# Adafruit_Feather_Zero_BLE_rev_B.net
KiCad netlist of a schematic drawn in EAGLE
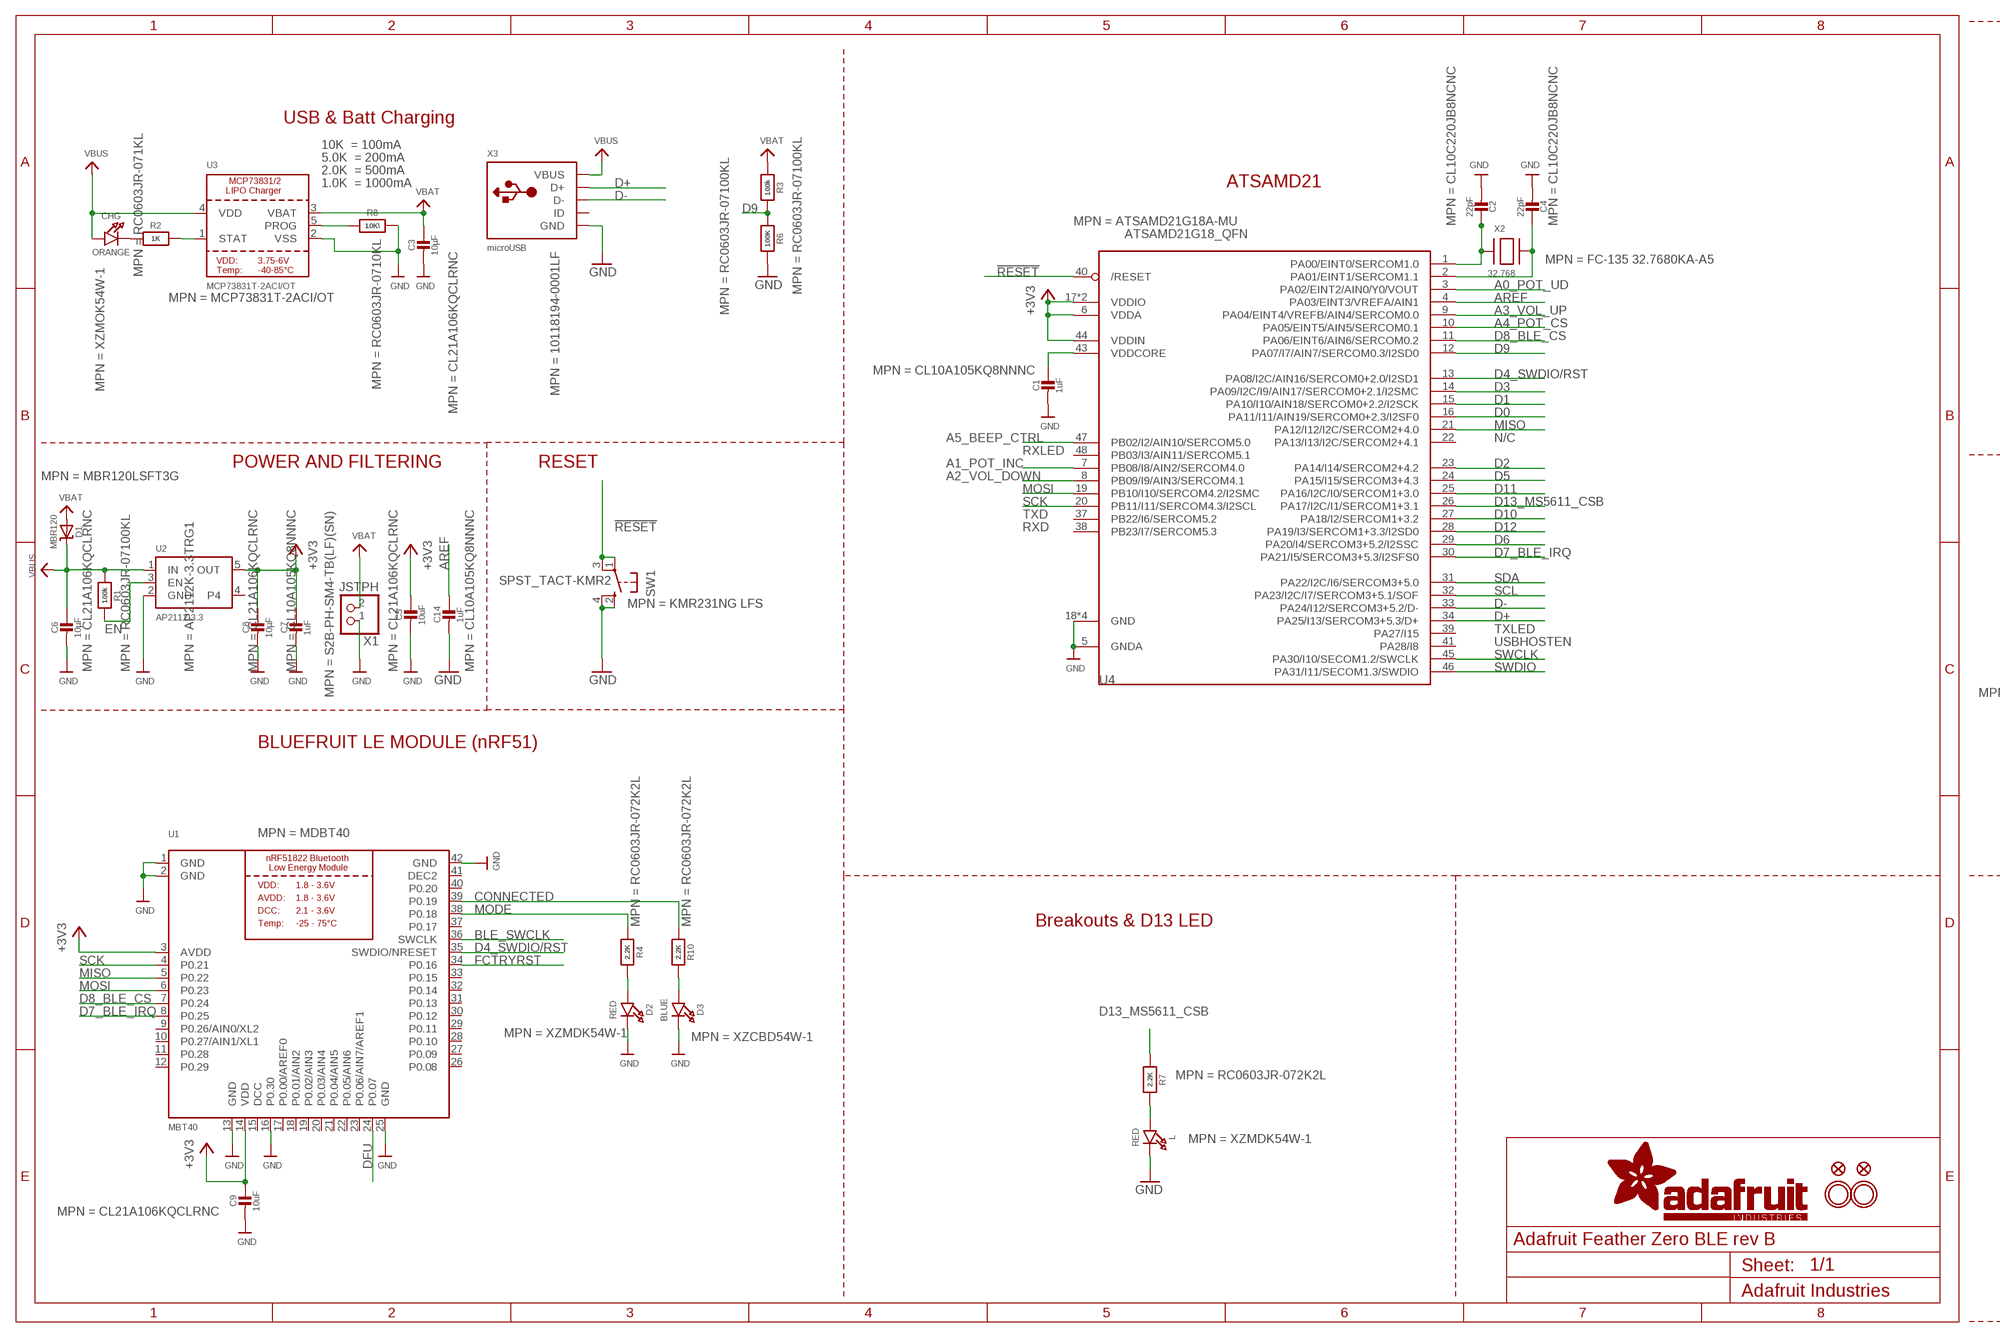
[diagram p0: schematic, sheet 1, part 1 of 2]
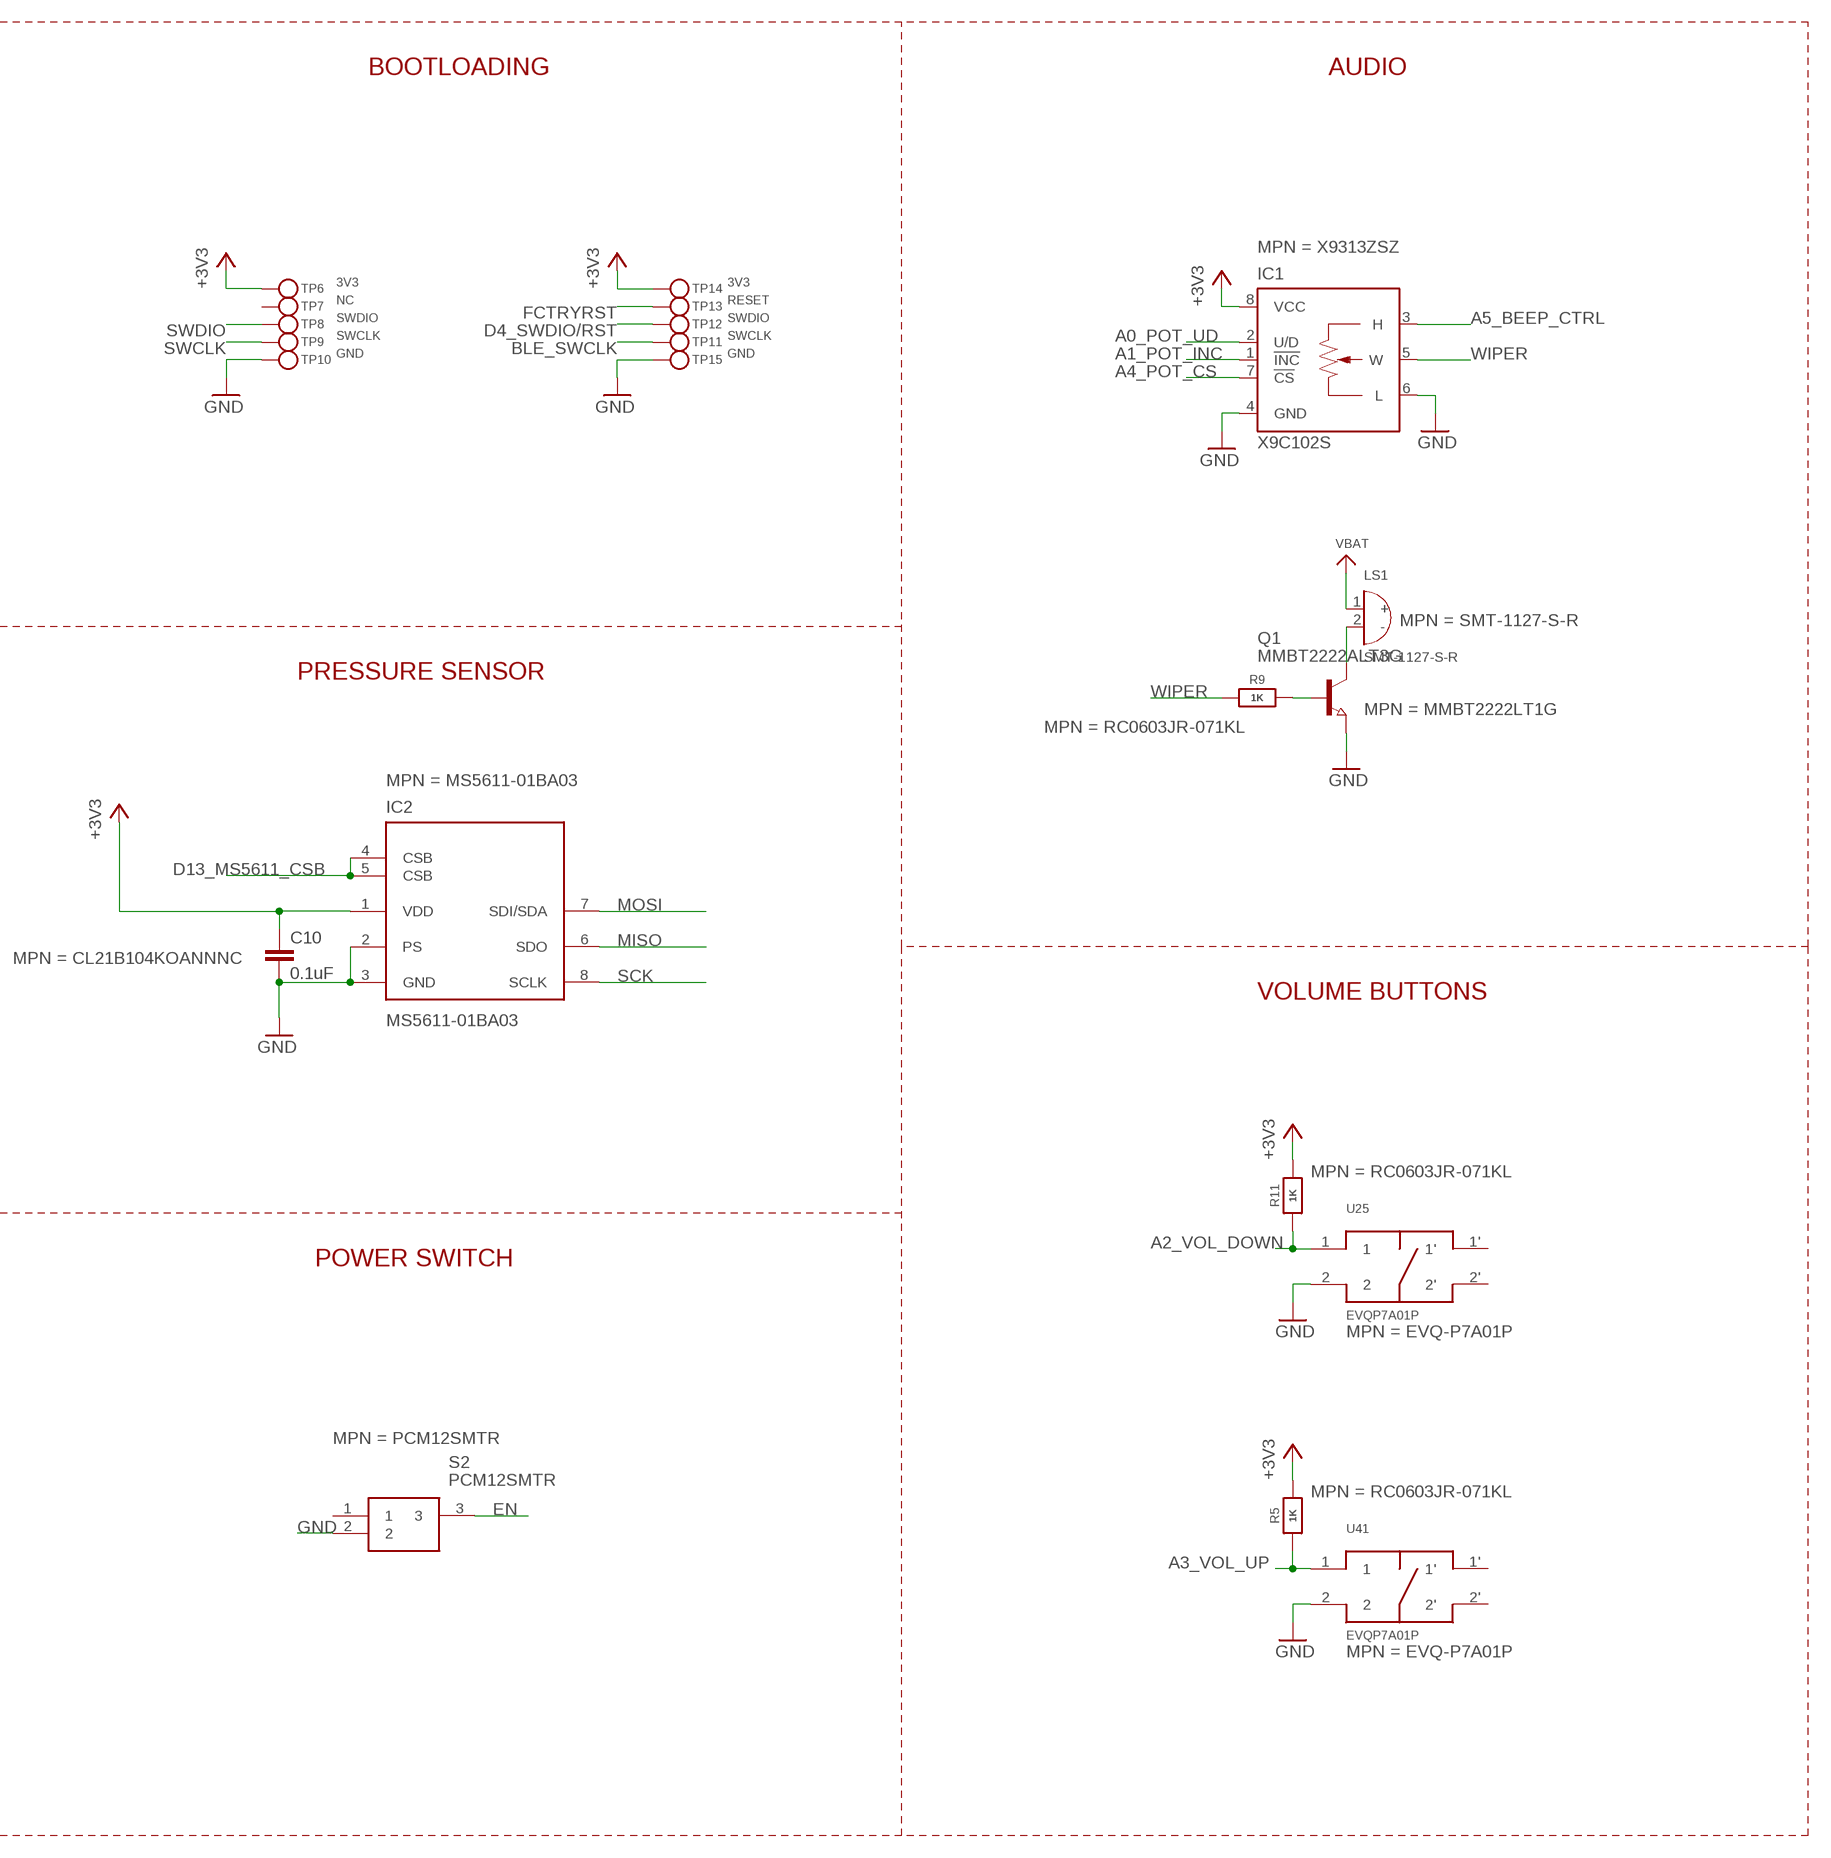
[diagram p1: schematic, sheet 1, part 2 of 2]

(export (version "E")
  (design (tool "Eeschema 10.0.6"))
  (components
    (comp (ref "C1")
      (value "1uF")
      (footprint "eagle-import:0603-NO")
      (fields (field (name "MPN") "CL10A105KQ8NNNC"))
      (libsource (lib "eagle-import") (part "CAP_CERAMIC0603_NO"))
    )
    (comp (ref "C2")
      (value "22pF")
      (footprint "eagle-import:0603-NO")
      (fields (field (name "MPN") "CL10C220JB8NCNC"))
      (libsource (lib "eagle-import") (part "CAP_CERAMIC0603_NO"))
    )
    (comp (ref "C3")
      (value "10µF")
      (footprint "eagle-import:0805-NO")
      (fields (field (name "MPN") "CL21A106KQCLRNC"))
      (libsource (lib "eagle-import") (part "CAP_CERAMIC0805-NOOUTLINE"))
    )
    (comp (ref "C4")
      (value "22pF")
      (footprint "eagle-import:0603-NO")
      (fields (field (name "MPN") "CL10C220JB8NCNC"))
      (libsource (lib "eagle-import") (part "CAP_CERAMIC0603_NO"))
    )
    (comp (ref "C5")
      (value "10uF")
      (footprint "eagle-import:0805-NO")
      (fields (field (name "MPN") "CL21A106KQCLRNC"))
      (libsource (lib "eagle-import") (part "CAP_CERAMIC0805-NOOUTLINE"))
    )
    (comp (ref "C6")
      (value "10µF")
      (footprint "eagle-import:0805-NO")
      (fields (field (name "MPN") "CL21A106KQCLRNC"))
      (libsource (lib "eagle-import") (part "CAP_CERAMIC0805-NOOUTLINE"))
    )
    (comp (ref "C7")
      (value "1uF")
      (footprint "eagle-import:0603-NO")
      (fields (field (name "MPN") "CL10A105KQ8NNNC"))
      (libsource (lib "eagle-import") (part "CAP_CERAMIC0603_NO"))
    )
    (comp (ref "C8")
      (value "10µF")
      (footprint "eagle-import:0805-NO")
      (fields (field (name "MPN") "CL21A106KQCLRNC"))
      (libsource (lib "eagle-import") (part "CAP_CERAMIC0805-NOOUTLINE"))
    )
    (comp (ref "C9")
      (value "10uF")
      (footprint "eagle-import:0805-NO")
      (fields (field (name "MPN") "CL21A106KQCLRNC"))
      (libsource (lib "eagle-import") (part "CAP_CERAMIC0805-NOOUTLINE"))
    )
    (comp (ref "C10")
      (value "0.1uF")
      (footprint "eagle-import:C0805K")
      (fields (field (name "MPN") "CL21B104KOANNNC"))
      (libsource (lib "eagle-import") (part "C-EUC0805K"))
    )
    (comp (ref "C14")
      (value "1uF")
      (footprint "eagle-import:0603-NO")
      (fields (field (name "MPN") "CL10A105KQ8NNNC"))
      (libsource (lib "eagle-import") (part "CAP_CERAMIC0603_NO"))
    )
    (comp (ref "CHG")
      (value "ORANGE")
      (footprint "eagle-import:CHIPLED_0805_NOOUTLINE")
      (fields (field (name "MPN") "XZMOK54W-1"))
      (libsource (lib "eagle-import") (part "LED0805_NOOUTLINE"))
    )
    (comp (ref "D1")
      (value "MBR120")
      (footprint "eagle-import:SOD-123")
      (fields (field (name "MPN") "MBR120LSFT3G"))
      (libsource (lib "eagle-import") (part "DIODE-SCHOTTKYSOD-123"))
    )
    (comp (ref "D2")
      (value "RED")
      (footprint "eagle-import:CHIPLED_0805_NOOUTLINE")
      (fields (field (name "MPN") "XZMDK54W-1"))
      (libsource (lib "eagle-import") (part "LED0805_NOOUTLINE"))
    )
    (comp (ref "D3")
      (value "BLUE")
      (footprint "eagle-import:CHIPLED_0805_NOOUTLINE")
      (fields (field (name "MPN") "XZCBD54W-1"))
      (libsource (lib "eagle-import") (part "LED0805_NOOUTLINE"))
    )
    (comp (ref "IC1")
      (value "X9C102S")
      (footprint "eagle-import:SOIC08")
      (fields
        (field (name "MF") "INTERSIL")
        (field (name "MPN") "X9C102SIZ")
        (field (name "MPN_1") "X9313ZSZ")
      )
      (libsource (lib "eagle-import") (part "X9C102S"))
    )
    (comp (ref "IC2")
      (value "MS5611-01BA03")
      (footprint "eagle-import:SON125P300X500X100-8N")
      (fields (field (name "MPN") "MS5611-01BA03"))
      (libsource (lib "eagle-import") (part "MS5611-01BA03UNO"))
    )
    (comp (ref "L")
      (value "RED")
      (footprint "eagle-import:CHIPLED_0805_NOOUTLINE")
      (fields (field (name "MPN") "XZMDK54W-1"))
      (libsource (lib "eagle-import") (part "LED0805_NOOUTLINE"))
    )
    (comp (ref "LS1")
      (value "SMT-1127-S-R")
      (footprint "eagle-import:XDCR_SMT-1127-S-R")
      (description "Black Passive Electromagnetic SMD Buzzer 3V 80mA 2700Hz 92dB 9x3.2mm")
      (fields
        (field (name "MF") "PUI Audio")
        (field (name "MP") "BOT-03D-BUJEON, SMT-1127-S-R")
        (field (name "MPN") "SMT-1127-S-R")
      )
      (libsource (lib "eagle-import") (part "SMT-1127-S-R"))
    )
    (comp (ref "Q1")
      (value "MMBT2222ALT3G")
      (footprint "eagle-import:SOT23")
      (fields (field (name "MPN") "MMBT2222LT1G"))
      (libsource (lib "eagle-import") (part "NPN-TRANSISTOR_SOT23"))
    )
    (comp (ref "R1")
      (value "100k")
      (footprint "eagle-import:0603-NO")
      (fields (field (name "MPN") "RC0603JR-07100KL"))
      (libsource (lib "eagle-import") (part "RESISTOR_0603_NOOUT"))
    )
    (comp (ref "R2")
      (value "1K")
      (footprint "eagle-import:0603-NO")
      (fields (field (name "MPN") "RC0603JR-071KL"))
      (libsource (lib "eagle-import") (part "RESISTOR_0603_NOOUT"))
    )
    (comp (ref "R3")
      (value "100k")
      (footprint "eagle-import:0603-NO")
      (fields (field (name "MPN") "RC0603JR-07100KL"))
      (libsource (lib "eagle-import") (part "RESISTOR_0603_NOOUT"))
    )
    (comp (ref "R4")
      (value "2.2K")
      (footprint "eagle-import:0603-NO")
      (fields (field (name "MPN") "RC0603JR-072K2L"))
      (libsource (lib "eagle-import") (part "RESISTOR_0603_NOOUT"))
    )
    (comp (ref "R5")
      (value "1K")
      (footprint "eagle-import:0603-NO")
      (fields (field (name "MPN") "RC0603JR-071KL"))
      (libsource (lib "eagle-import") (part "RESISTOR_0603_NOOUT"))
    )
    (comp (ref "R6")
      (value "100K")
      (footprint "eagle-import:0603-NO")
      (fields (field (name "MPN") "RC0603JR-07100KL"))
      (libsource (lib "eagle-import") (part "RESISTOR_0603_NOOUT"))
    )
    (comp (ref "R7")
      (value "2.2K")
      (footprint "eagle-import:0603-NO")
      (fields (field (name "MPN") "RC0603JR-072K2L"))
      (libsource (lib "eagle-import") (part "RESISTOR_0603_NOOUT"))
    )
    (comp (ref "R8")
      (value "10K\\")
      (footprint "eagle-import:0603-NO")
      (fields (field (name "MPN") "RC0603JR-0710KL"))
      (libsource (lib "eagle-import") (part "RESISTOR_0603_NOOUT"))
    )
    (comp (ref "R9")
      (value "1K")
      (footprint "eagle-import:0603-NO")
      (fields (field (name "MPN") "RC0603JR-071KL"))
      (libsource (lib "eagle-import") (part "RESISTOR_0603_NOOUT"))
    )
    (comp (ref "R10")
      (value "2.2K")
      (footprint "eagle-import:0603-NO")
      (fields (field (name "MPN") "RC0603JR-072K2L"))
      (libsource (lib "eagle-import") (part "RESISTOR_0603_NOOUT"))
    )
    (comp (ref "R11")
      (value "1K")
      (footprint "eagle-import:0603-NO")
      (fields (field (name "MPN") "RC0603JR-071KL"))
      (libsource (lib "eagle-import") (part "RESISTOR_0603_NOOUT"))
    )
    (comp (ref "S2")
      (value "PCM12SMTR")
      (footprint "eagle-import:PCM12SMTR_1")
      (fields (field (name "RS_PART_NUMBER") "7931721P") (field (name "MPN") "PCM12SMTR"))
      (libsource (lib "eagle-import") (part "PCM12SMTR"))
    )
    (comp (ref "SW1")
      (value "SPST_TACT-KMR2")
      (footprint "eagle-import:KMR2")
      (fields (field (name "MPN") "KMR231NG LFS"))
      (libsource (lib "eagle-import") (part "SPST_TACT-KMR2"))
    )
    (comp (ref "TP6")
      (value "3V3")
      (footprint "eagle-import:PAD-1.5X2.0")
      (libsource (lib "eagle-import") (part "TESTPOINT1.5X2.0MM_NOCREAM"))
    )
    (comp (ref "TP7")
      (value "NC")
      (footprint "eagle-import:PAD-1.5X2.0")
      (libsource (lib "eagle-import") (part "TESTPOINT1.5X2.0MM_NOCREAM"))
    )
    (comp (ref "TP8")
      (value "SWDIO")
      (footprint "eagle-import:PAD-1.5X2.0")
      (libsource (lib "eagle-import") (part "TESTPOINT1.5X2.0MM_NOCREAM"))
    )
    (comp (ref "TP9")
      (value "SWCLK")
      (footprint "eagle-import:PAD-1.5X2.0")
      (libsource (lib "eagle-import") (part "TESTPOINT1.5X2.0MM_NOCREAM"))
    )
    (comp (ref "TP10")
      (value "GND")
      (footprint "eagle-import:PAD-1.5X2.0")
      (libsource (lib "eagle-import") (part "TESTPOINT1.5X2.0MM_NOCREAM"))
    )
    (comp (ref "TP11")
      (value "SWCLK")
      (footprint "eagle-import:PAD-1.5X2.0")
      (libsource (lib "eagle-import") (part "TESTPOINT1.5X2.0MM_NOCREAM"))
    )
    (comp (ref "TP12")
      (value "SWDIO")
      (footprint "eagle-import:PAD-1.5X2.0")
      (libsource (lib "eagle-import") (part "TESTPOINT1.5X2.0MM_NOCREAM"))
    )
    (comp (ref "TP13")
      (value "RESET")
      (footprint "eagle-import:PAD-1.5X2.0")
      (libsource (lib "eagle-import") (part "TESTPOINT1.5X2.0MM_NOCREAM"))
    )
    (comp (ref "TP14")
      (value "3V3")
      (footprint "eagle-import:PAD-1.5X2.0")
      (libsource (lib "eagle-import") (part "TESTPOINT1.5X2.0MM_NOCREAM"))
    )
    (comp (ref "TP15")
      (value "GND")
      (footprint "eagle-import:PAD-1.5X2.0")
      (libsource (lib "eagle-import") (part "TESTPOINT1.5X2.0MM_NOCREAM"))
    )
    (comp (ref "U$31")
      (value "MOUNTINGHOLE2.5")
      (footprint "eagle-import:MOUNTINGHOLE_2.5_PLATED")
      (libsource (lib "eagle-import") (part "MOUNTINGHOLE2.5"))
    )
    (comp (ref "U$32")
      (value "MOUNTINGHOLE2.5")
      (footprint "eagle-import:MOUNTINGHOLE_2.5_PLATED")
      (libsource (lib "eagle-import") (part "MOUNTINGHOLE2.5"))
    )
    (comp (ref "U$34")
      (value "FIDUCIAL\"\"")
      (footprint "eagle-import:FIDUCIAL_1MM")
      (libsource (lib "eagle-import") (part "FIDUCIAL{dblquote}{dblquote}"))
    )
    (comp (ref "U$35")
      (value "FIDUCIAL\"\"")
      (footprint "eagle-import:FIDUCIAL_1MM")
      (libsource (lib "eagle-import") (part "FIDUCIAL{dblquote}{dblquote}"))
    )
    (comp (ref "U1")
      (value "MBT40")
      (footprint "eagle-import:BLE_MODULE_RAYTAC_MDBT40")
      (fields (field (name "MPN") "MDBT40"))
      (libsource (lib "eagle-import") (part "NRF51822_MODULE_MDBT40"))
    )
    (comp (ref "U2")
      (value "AP2112-3.3")
      (footprint "eagle-import:SOT23-5")
      (fields (field (name "MPN") "AP2112K-3.3TRG1"))
      (libsource (lib "eagle-import") (part "VREG_SOT23-5"))
    )
    (comp (ref "U3")
      (value "MCP73831T-2ACI/OT")
      (footprint "eagle-import:SOT23-5")
      (fields (field (name "MPN") "MCP73831T-2ACI/OT"))
      (libsource (lib "eagle-import") (part "MCP73831/2"))
    )
    (comp (ref "U4")
      (value "ATSAMD21G18_QFN")
      (footprint "eagle-import:TQFN48_7MM")
      (fields (field (name "MPN") "ATSAMD21G18A-MU"))
      (libsource (lib "eagle-import") (part "ATSAMD21J_QFN"))
    )
    (comp (ref "U25")
      (value "EVQP7A01P")
      (footprint "eagle-import:EVQP7A01P")
      (fields (field (name "MPN") "EVQ-P7A01P"))
      (libsource (lib "eagle-import") (part "EVQP7A01P"))
    )
    (comp (ref "U41")
      (value "EVQP7A01P")
      (footprint "eagle-import:EVQP7A01P")
      (fields (field (name "MPN") "EVQ-P7A01P"))
      (libsource (lib "eagle-import") (part "EVQP7A01P"))
    )
    (comp (ref "X1")
      (value "JSTPH")
      (footprint "eagle-import:JSTPH2")
      (fields (field (name "MPN") "S2B-PH-SM4-TB(LF)(SN)"))
      (libsource (lib "eagle-import") (part "CON_JST_PH_2PIN"))
    )
    (comp (ref "X2")
      (value "32.768")
      (footprint "eagle-import:XTAL3215")
      (fields (field (name "MPN") "FC-135 32.7680KA-A5"))
      (libsource (lib "eagle-import") (part "XTAL-3.2X1.5"))
    )
    (comp (ref "X3")
      (value "microUSB")
      (footprint "eagle-import:4UCONN_20329_V2")
      (fields (field (name "MPN") "10118194-0001LF"))
      (libsource (lib "eagle-import") (part "USB_MICRO_20329_V2"))
    )
  )
  (nets
    (net (code "1") (name "+3V3") (class "Default")
      (node (ref "C10") (pin "1") (pinfunction "1_1") (pintype "passive"))
      (node (ref "C5") (pin "1") (pinfunction "1_1") (pintype "passive"))
      (node (ref "C7") (pin "1") (pinfunction "1_1") (pintype "passive"))
      (node (ref "C8") (pin "1") (pinfunction "1_1") (pintype "passive"))
      (node (ref "C9") (pin "1") (pinfunction "1_1") (pintype "passive"))
      (node (ref "IC1") (pin "8") (pinfunction "VCC_8") (pintype "power_in"))
      (node (ref "IC2") (pin "1") (pinfunction "VDD_1") (pintype "power_in"))
      (node (ref "R11") (pin "2") (pinfunction "2_2") (pintype "passive"))
      (node (ref "R5") (pin "2") (pinfunction "2_2") (pintype "passive"))
      (node (ref "TP14") (pin "P$1") (pinfunction "P$1_P$1") (pintype "bidirectional"))
      (node (ref "TP6") (pin "P$1") (pinfunction "P$1_P$1") (pintype "bidirectional"))
      (node (ref "U1") (pin "14") (pinfunction "VDD_14") (pintype "power_in"))
      (node (ref "U1") (pin "3") (pinfunction "AVDD_3") (pintype "power_in"))
      (node (ref "U2") (pin "5") (pinfunction "OUT_5") (pintype "power_in"))
      (node (ref "U4") (pin "17") (pinfunction "VDDIO_17") (pintype "power_in"))
      (node (ref "U4") (pin "36") (pinfunction "VDDIO_36") (pintype "power_in"))
      (node (ref "U4") (pin "44") (pinfunction "VDDIN_44") (pintype "power_in"))
      (node (ref "U4") (pin "6") (pinfunction "VDDA_6") (pintype "power_in"))
    )
    (net (code "2") (name "/A0_POT_UD") (class "Default")
      (node (ref "IC1") (pin "2") (pinfunction "U/D_2") (pintype "input"))
      (node (ref "U4") (pin "3") (pinfunction "PA02/EINT2/AIN0/Y0/VOUT_3") (pintype "bidirectional"))
    )
    (net (code "3") (name "/A1_POT_INC") (class "Default")
      (node (ref "IC1") (pin "1") (pinfunction "~{INC}_1") (pintype "input"))
      (node (ref "U4") (pin "7") (pinfunction "PB08/I8/AIN2/SERCOM4.0_7") (pintype "bidirectional"))
    )
    (net (code "4") (name "/A2_VOL_DOWN") (class "Default")
      (node (ref "R11") (pin "1") (pinfunction "1_1") (pintype "passive"))
      (node (ref "U25") (pin "1") (pinfunction "1_1") (pintype "bidirectional"))
      (node (ref "U4") (pin "8") (pinfunction "PB09/I9/AIN3/SERCOM4.1_8") (pintype "bidirectional"))
    )
    (net (code "5") (name "/A3_VOL_UP") (class "Default")
      (node (ref "R5") (pin "1") (pinfunction "1_1") (pintype "passive"))
      (node (ref "U4") (pin "9") (pinfunction "PA04/EINT4/VREFB/AIN4/SERCOM0.0_9") (pintype "bidirectional"))
      (node (ref "U41") (pin "1") (pinfunction "1_1") (pintype "bidirectional"))
    )
    (net (code "6") (name "/A4_POT_CS") (class "Default")
      (node (ref "IC1") (pin "7") (pinfunction "~{CS}_7") (pintype "input"))
      (node (ref "U4") (pin "10") (pinfunction "PA05/EINT5/AIN5/SERCOM0.1_10") (pintype "bidirectional"))
    )
    (net (code "7") (name "/A5_BEEP_CTRL") (class "Default")
      (node (ref "IC1") (pin "3") (pinfunction "H_3") (pintype "passive"))
      (node (ref "U4") (pin "47") (pinfunction "PB02/I2/AIN10/SERCOM5.0_47") (pintype "bidirectional"))
    )
    (net (code "8") (name "/AREF") (class "Default")
      (node (ref "C14") (pin "1") (pinfunction "1_1") (pintype "passive"))
      (node (ref "U4") (pin "4") (pinfunction "PA03/EINT3/VREFA/AIN1_4") (pintype "bidirectional"))
    )
    (net (code "9") (name "/BLE_SWCLK") (class "Default")
      (node (ref "TP11") (pin "P$1") (pinfunction "P$1_P$1") (pintype "bidirectional"))
      (node (ref "U1") (pin "36") (pinfunction "SWCLK_36") (pintype "bidirectional"))
    )
    (net (code "10") (name "/CONNECTED") (class "Default")
      (node (ref "R10") (pin "1") (pinfunction "1_1") (pintype "passive"))
      (node (ref "U1") (pin "39") (pinfunction "P0.19_39") (pintype "bidirectional"))
    )
    (net (code "11") (name "/D+") (class "Default")
      (node (ref "U4") (pin "34") (pinfunction "PA25/I13/SERCOM3+5.3/D+_34") (pintype "bidirectional"))
      (node (ref "X3") (pin "D+") (pinfunction "D+_D+") (pintype "bidirectional"))
    )
    (net (code "12") (name "/D-") (class "Default")
      (node (ref "U4") (pin "33") (pinfunction "PA24/I12/SERCOM3+5.2/D-_33") (pintype "bidirectional"))
      (node (ref "X3") (pin "D-") (pinfunction "D-_D-") (pintype "bidirectional"))
    )
    (net (code "13") (name "/D0") (class "Default")
      (node (ref "U4") (pin "16") (pinfunction "PA11/I11/AIN19/SERCOM0+2.3/I2SF0_16") (pintype "bidirectional"))
    )
    (net (code "14") (name "/D1") (class "Default")
      (node (ref "U4") (pin "15") (pinfunction "PA10/I10/AIN18/SERCOM0+2.2/I2SCK_15") (pintype "bidirectional"))
    )
    (net (code "15") (name "/D2") (class "Default")
      (node (ref "U4") (pin "23") (pinfunction "PA14/I14/SERCOM2+4.2_23") (pintype "bidirectional"))
    )
    (net (code "16") (name "/D3") (class "Default")
      (node (ref "U4") (pin "14") (pinfunction "PA09/I2C/I9/AIN17/SERCOM0+2.1/I2SMC_14") (pintype "bidirectional"))
    )
    (net (code "17") (name "/D4_SWDIO{slash}RST") (class "Default")
      (node (ref "TP12") (pin "P$1") (pinfunction "P$1_P$1") (pintype "bidirectional"))
      (node (ref "U1") (pin "35") (pinfunction "SWDIO/NRESET_35") (pintype "bidirectional"))
      (node (ref "U4") (pin "13") (pinfunction "PA08/I2C/AIN16/SERCOM0+2.0/I2SD1_13") (pintype "bidirectional"))
    )
    (net (code "18") (name "/D5") (class "Default")
      (node (ref "U4") (pin "24") (pinfunction "PA15/I15/SERCOM3+4.3_24") (pintype "bidirectional"))
    )
    (net (code "19") (name "/D6") (class "Default")
      (node (ref "U4") (pin "29") (pinfunction "PA20/I4/SERCOM3+5.2/I2SSC_29") (pintype "bidirectional"))
    )
    (net (code "20") (name "/D7_BLE_IRQ") (class "Default")
      (node (ref "U1") (pin "8") (pinfunction "P0.25_8") (pintype "bidirectional"))
      (node (ref "U4") (pin "30") (pinfunction "PA21/I5/SERCOM3+5.3/I2SFS0_30") (pintype "bidirectional"))
    )
    (net (code "21") (name "/D8_BLE_CS") (class "Default")
      (node (ref "U1") (pin "7") (pinfunction "P0.24_7") (pintype "bidirectional"))
      (node (ref "U4") (pin "11") (pinfunction "PA06/EINT6/AIN6/SERCOM0.2_11") (pintype "bidirectional"))
    )
    (net (code "22") (name "/D9") (class "Default")
      (node (ref "R3") (pin "2") (pinfunction "2_2") (pintype "passive"))
      (node (ref "R6") (pin "1") (pinfunction "1_1") (pintype "passive"))
      (node (ref "U4") (pin "12") (pinfunction "PA07/I7/AIN7/SERCOM0.3/I2SD0_12") (pintype "bidirectional"))
    )
    (net (code "23") (name "/D10") (class "Default")
      (node (ref "U4") (pin "27") (pinfunction "PA18/I2/SERCOM1+3.2_27") (pintype "bidirectional"))
    )
    (net (code "24") (name "/D11") (class "Default")
      (node (ref "U4") (pin "25") (pinfunction "PA16/I2C/I0/SERCOM1+3.0_25") (pintype "bidirectional"))
    )
    (net (code "25") (name "/D12") (class "Default")
      (node (ref "U4") (pin "28") (pinfunction "PA19/I3/SERCOM1+3.3/I2SD0_28") (pintype "bidirectional"))
    )
    (net (code "26") (name "/D13_MS5611_CSB") (class "Default")
      (node (ref "IC2") (pin "4") (pinfunction "CSB_4") (pintype "input"))
      (node (ref "IC2") (pin "5") (pinfunction "CSB_5") (pintype "input"))
      (node (ref "R7") (pin "1") (pinfunction "1_1") (pintype "passive"))
      (node (ref "U4") (pin "26") (pinfunction "PA17/I2C/I1/SERCOM1+3.1_26") (pintype "bidirectional"))
    )
    (net (code "27") (name "/DCC") (class "Default")
      (node (ref "U1") (pin "15") (pinfunction "DCC_15") (pintype "power_in"))
    )
    (net (code "28") (name "/DEC2") (class "Default")
      (node (ref "U1") (pin "41") (pinfunction "DEC2_41") (pintype "power_in"))
    )
    (net (code "29") (name "/DFU") (class "Default")
      (node (ref "U1") (pin "24") (pinfunction "P0.07_24") (pintype "bidirectional"))
    )
    (net (code "30") (name "/EN") (class "Default")
      (node (ref "R1") (pin "2") (pinfunction "2_2") (pintype "passive"))
      (node (ref "S2") (pin "3") (pinfunction "3_3") (pintype "input"))
      (node (ref "U2") (pin "3") (pinfunction "EN_3") (pintype "input"))
    )
    (net (code "31") (name "/FCTRYRST") (class "Default")
      (node (ref "TP13") (pin "P$1") (pinfunction "P$1_P$1") (pintype "bidirectional"))
      (node (ref "U1") (pin "34") (pinfunction "P0.16_34") (pintype "bidirectional"))
    )
    (net (code "32") (name "/MISO") (class "Default")
      (node (ref "IC2") (pin "6") (pinfunction "SDO_6") (pintype "output"))
      (node (ref "U1") (pin "5") (pinfunction "P0.22_5") (pintype "bidirectional"))
      (node (ref "U4") (pin "21") (pinfunction "PA12/I12/I2C/SERCOM2+4.0_21") (pintype "bidirectional"))
    )
    (net (code "33") (name "/MODE") (class "Default")
      (node (ref "R4") (pin "1") (pinfunction "1_1") (pintype "passive"))
      (node (ref "U1") (pin "38") (pinfunction "P0.18_38") (pintype "bidirectional"))
    )
    (net (code "34") (name "/MOSI") (class "Default")
      (node (ref "IC2") (pin "7") (pinfunction "SDI/SDA_7") (pintype "bidirectional"))
      (node (ref "U1") (pin "6") (pinfunction "P0.23_6") (pintype "bidirectional"))
      (node (ref "U4") (pin "19") (pinfunction "PB10/I10/SERCOM4.2/I2SMC_19") (pintype "bidirectional"))
    )
    (net (code "35") (name "/SCK") (class "Default")
      (node (ref "IC2") (pin "8") (pinfunction "SCLK_8") (pintype "input"))
      (node (ref "U1") (pin "4") (pinfunction "P0.21_4") (pintype "bidirectional"))
      (node (ref "U4") (pin "20") (pinfunction "PB11/I11/SERCOM4.3/I2SCL_20") (pintype "bidirectional"))
    )
    (net (code "36") (name "/SCL") (class "Default")
      (node (ref "U4") (pin "32") (pinfunction "PA23/I2C/I7/SERCOM3+5.1/SOF_32") (pintype "bidirectional"))
    )
    (net (code "37") (name "/SDA") (class "Default")
      (node (ref "U4") (pin "31") (pinfunction "PA22/I2C/I6/SERCOM3+5.0_31") (pintype "bidirectional"))
    )
    (net (code "38") (name "/SWCLK") (class "Default")
      (node (ref "TP9") (pin "P$1") (pinfunction "P$1_P$1") (pintype "bidirectional"))
      (node (ref "U4") (pin "45") (pinfunction "PA30/I10/SECOM1.2/SWCLK_45") (pintype "bidirectional"))
    )
    (net (code "39") (name "/SWDIO") (class "Default")
      (node (ref "TP8") (pin "P$1") (pinfunction "P$1_P$1") (pintype "bidirectional"))
      (node (ref "U4") (pin "46") (pinfunction "PA31/I11/SECOM1.3/SWDIO_46") (pintype "bidirectional"))
    )
    (net (code "40") (name "/WIPER") (class "Default")
      (node (ref "IC1") (pin "5") (pinfunction "W_5") (pintype "passive"))
      (node (ref "R9") (pin "1") (pinfunction "1_1") (pintype "passive"))
    )
    (net (code "41") (name "/~{RESET}") (class "Default")
      (node (ref "SW1") (pin "1") (pinfunction "P_1") (pintype "passive"))
      (node (ref "SW1") (pin "3") (pinfunction "P1_3") (pintype "passive"))
      (node (ref "U4") (pin "40") (pinfunction "/RESET_40") (pintype "bidirectional"))
    )
    (net (code "42") (name "GND") (class "Default")
      (node (ref "C1") (pin "2") (pinfunction "2_2") (pintype "passive"))
      (node (ref "C10") (pin "2") (pinfunction "2_2") (pintype "passive"))
      (node (ref "C14") (pin "2") (pinfunction "2_2") (pintype "passive"))
      (node (ref "C2") (pin "2") (pinfunction "2_2") (pintype "passive"))
      (node (ref "C3") (pin "2") (pinfunction "2_2") (pintype "passive"))
      (node (ref "C4") (pin "2") (pinfunction "2_2") (pintype "passive"))
      (node (ref "C5") (pin "2") (pinfunction "2_2") (pintype "passive"))
      (node (ref "C6") (pin "2") (pinfunction "2_2") (pintype "passive"))
      (node (ref "C7") (pin "2") (pinfunction "2_2") (pintype "passive"))
      (node (ref "C8") (pin "2") (pinfunction "2_2") (pintype "passive"))
      (node (ref "C9") (pin "2") (pinfunction "2_2") (pintype "passive"))
      (node (ref "D2") (pin "C") (pinfunction "C_C") (pintype "passive"))
      (node (ref "D3") (pin "C") (pinfunction "C_C") (pintype "passive"))
      (node (ref "IC1") (pin "4") (pinfunction "GND_4") (pintype "power_in"))
      (node (ref "IC1") (pin "6") (pinfunction "L_6") (pintype "passive"))
      (node (ref "IC2") (pin "2") (pinfunction "PS_2") (pintype "input"))
      (node (ref "IC2") (pin "3") (pinfunction "GND_3") (pintype "power_in"))
      (node (ref "L") (pin "C") (pinfunction "C_C") (pintype "passive"))
      (node (ref "Q1") (pin "2") (pinfunction "E_2") (pintype "passive"))
      (node (ref "R6") (pin "2") (pinfunction "2_2") (pintype "passive"))
      (node (ref "R8") (pin "2") (pinfunction "2_2") (pintype "passive"))
      (node (ref "S2") (pin "2") (pinfunction "2_2") (pintype "input"))
      (node (ref "SW1") (pin "2") (pinfunction "S_2") (pintype "passive"))
      (node (ref "SW1") (pin "4") (pinfunction "S1_4") (pintype "passive"))
      (node (ref "TP10") (pin "P$1") (pinfunction "P$1_P$1") (pintype "bidirectional"))
      (node (ref "TP15") (pin "P$1") (pinfunction "P$1_P$1") (pintype "bidirectional"))
      (node (ref "U1") (pin "1") (pinfunction "GND_1") (pintype "power_in"))
      (node (ref "U1") (pin "13") (pinfunction "GND_13") (pintype "power_in"))
      (node (ref "U1") (pin "16") (pinfunction "P0.30_16") (pintype "bidirectional"))
      (node (ref "U1") (pin "2") (pinfunction "GND_2") (pintype "power_in"))
      (node (ref "U1") (pin "25") (pinfunction "GND_25") (pintype "power_in"))
      (node (ref "U1") (pin "42") (pinfunction "GND_42") (pintype "power_in"))
      (node (ref "U2") (pin "2") (pinfunction "GND_2") (pintype "power_in"))
      (node (ref "U25") (pin "2") (pinfunction "2_2") (pintype "bidirectional"))
      (node (ref "U3") (pin "2") (pinfunction "VSS_2") (pintype "power_in"))
      (node (ref "U4") (pin "18") (pinfunction "GND_18") (pintype "power_in"))
      (node (ref "U4") (pin "35") (pinfunction "GND_35") (pintype "power_in"))
      (node (ref "U4") (pin "42") (pinfunction "GND_42") (pintype "power_in"))
      (node (ref "U4") (pin "5") (pinfunction "GNDA_5") (pintype "power_in"))
      (node (ref "U4") (pin "THERMAL") (pinfunction "GND_THERMAL") (pintype "power_in"))
      (node (ref "U41") (pin "2") (pinfunction "2_2") (pintype "bidirectional"))
      (node (ref "X1") (pin "1") (pinfunction "1_1") (pintype "passive"))
      (node (ref "X3") (pin "BASE@1") (pinfunction "GND_BASE@1") (pintype "power_in"))
      (node (ref "X3") (pin "BASE@2") (pinfunction "GND_BASE@2") (pintype "power_in"))
      (node (ref "X3") (pin "GND") (pinfunction "GND_GND") (pintype "power_in"))
      (node (ref "X3") (pin "SPRT@1") (pinfunction "GND_SPRT@1") (pintype "power_in"))
      (node (ref "X3") (pin "SPRT@2") (pinfunction "GND_SPRT@2") (pintype "power_in"))
      (node (ref "X3") (pin "SPRT@3") (pinfunction "GND_SPRT@3") (pintype "power_in"))
      (node (ref "X3") (pin "SPRT@4") (pinfunction "GND_SPRT@4") (pintype "power_in"))
    )
    (net (code "43") (name "Net-(CHG-PadC)") (class "Default")
      (node (ref "CHG") (pin "C") (pinfunction "C_C") (pintype "passive"))
      (node (ref "R2") (pin "1") (pinfunction "1_1") (pintype "passive"))
    )
    (net (code "44") (name "Net-(D2-PadA)") (class "Default")
      (node (ref "D2") (pin "A") (pinfunction "A_A") (pintype "passive"))
      (node (ref "R4") (pin "2") (pinfunction "2_2") (pintype "passive"))
    )
    (net (code "45") (name "Net-(D3-PadA)") (class "Default")
      (node (ref "D3") (pin "A") (pinfunction "A_A") (pintype "passive"))
      (node (ref "R10") (pin "2") (pinfunction "2_2") (pintype "passive"))
    )
    (net (code "46") (name "Net-(L-PadA)") (class "Default")
      (node (ref "L") (pin "A") (pinfunction "A_A") (pintype "passive"))
      (node (ref "R7") (pin "2") (pinfunction "2_2") (pintype "passive"))
    )
    (net (code "47") (name "Net-(LS1--)") (class "Default")
      (node (ref "LS1") (pin "2") (pinfunction "-_2") (pintype "passive"))
      (node (ref "Q1") (pin "3") (pinfunction "C_3") (pintype "passive"))
    )
    (net (code "48") (name "Net-(Q1-B)") (class "Default")
      (node (ref "Q1") (pin "1") (pinfunction "B_1") (pintype "passive"))
      (node (ref "R9") (pin "2") (pinfunction "2_2") (pintype "passive"))
    )
    (net (code "49") (name "Net-(U3-PROG)") (class "Default")
      (node (ref "R8") (pin "1") (pinfunction "1_1") (pintype "passive"))
      (node (ref "U3") (pin "5") (pinfunction "PROG_5") (pintype "input"))
    )
    (net (code "50") (name "Net-(U3-STAT)") (class "Default")
      (node (ref "R2") (pin "2") (pinfunction "2_2") (pintype "passive"))
      (node (ref "U3") (pin "1") (pinfunction "STAT_1") (pintype "output"))
    )
    (net (code "51") (name "Net-(U4-PA00{slash}EINT0{slash}SERCOM1.0)") (class "Default")
      (node (ref "C2") (pin "1") (pinfunction "1_1") (pintype "passive"))
      (node (ref "U4") (pin "1") (pinfunction "PA00/EINT0/SERCOM1.0_1") (pintype "bidirectional"))
      (node (ref "X2") (pin "P$1") (pinfunction "P$1_P$1") (pintype "bidirectional"))
    )
    (net (code "52") (name "Net-(U4-PA01{slash}EINT1{slash}SERCOM1.1)") (class "Default")
      (node (ref "C4") (pin "1") (pinfunction "1_1") (pintype "passive"))
      (node (ref "U4") (pin "2") (pinfunction "PA01/EINT1/SERCOM1.1_2") (pintype "bidirectional"))
      (node (ref "X2") (pin "P$2") (pinfunction "P$2_P$2") (pintype "bidirectional"))
    )
    (net (code "53") (name "Net-(U4-VDDCORE)") (class "Default")
      (node (ref "C1") (pin "1") (pinfunction "1_1") (pintype "passive"))
      (node (ref "U4") (pin "43") (pinfunction "VDDCORE_43") (pintype "power_in"))
    )
    (net (code "54") (name "VBAT") (class "Default")
      (node (ref "C3") (pin "1") (pinfunction "1_1") (pintype "passive"))
      (node (ref "D1") (pin "A") (pinfunction "A_A") (pintype "passive"))
      (node (ref "LS1") (pin "1") (pinfunction "+_1") (pintype "passive"))
      (node (ref "R3") (pin "1") (pinfunction "1_1") (pintype "passive"))
      (node (ref "U3") (pin "3") (pinfunction "VBAT_3") (pintype "power_in"))
      (node (ref "X1") (pin "2") (pinfunction "2_2") (pintype "passive"))
    )
    (net (code "55") (name "VBUS") (class "Default")
      (node (ref "C6") (pin "1") (pinfunction "1_1") (pintype "passive"))
      (node (ref "CHG") (pin "A") (pinfunction "A_A") (pintype "passive"))
      (node (ref "D1") (pin "C") (pinfunction "C_C") (pintype "passive"))
      (node (ref "R1") (pin "1") (pinfunction "1_1") (pintype "passive"))
      (node (ref "U2") (pin "1") (pinfunction "IN_1") (pintype "power_in"))
      (node (ref "U3") (pin "4") (pinfunction "VDD_4") (pintype "power_in"))
      (node (ref "X3") (pin "VBUS") (pinfunction "VBUS_VBUS") (pintype "power_in"))
    )
    (net (code "56") (name "unconnected-(S2-Pad1)") (class "Default")
      (node (ref "S2") (pin "1") (pinfunction "1_1") (pintype "input"))
    )
    (net (code "57") (name "unconnected-(TP7-PadP$1)") (class "Default")
      (node (ref "TP7") (pin "P$1") (pinfunction "P$1_P$1") (pintype "bidirectional"))
    )
    (net (code "58") (name "unconnected-(U1-P0.00{slash}AREF0-Pad17)") (class "Default")
      (node (ref "U1") (pin "17") (pinfunction "P0.00/AREF0_17") (pintype "bidirectional"))
    )
    (net (code "59") (name "unconnected-(U1-P0.01{slash}AIN2-Pad18)") (class "Default")
      (node (ref "U1") (pin "18") (pinfunction "P0.01/AIN2_18") (pintype "bidirectional"))
    )
    (net (code "60") (name "unconnected-(U1-P0.02{slash}AIN3-Pad19)") (class "Default")
      (node (ref "U1") (pin "19") (pinfunction "P0.02/AIN3_19") (pintype "bidirectional"))
    )
    (net (code "61") (name "unconnected-(U1-P0.03{slash}AIN4-Pad20)") (class "Default")
      (node (ref "U1") (pin "20") (pinfunction "P0.03/AIN4_20") (pintype "bidirectional"))
    )
    (net (code "62") (name "unconnected-(U1-P0.04{slash}AIN5-Pad21)") (class "Default")
      (node (ref "U1") (pin "21") (pinfunction "P0.04/AIN5_21") (pintype "bidirectional"))
    )
    (net (code "63") (name "unconnected-(U1-P0.05{slash}AIN6-Pad22)") (class "Default")
      (node (ref "U1") (pin "22") (pinfunction "P0.05/AIN6_22") (pintype "bidirectional"))
    )
    (net (code "64") (name "unconnected-(U1-P0.06{slash}AIN7{slash}AREF1-Pad23)") (class "Default")
      (node (ref "U1") (pin "23") (pinfunction "P0.06/AIN7/AREF1_23") (pintype "bidirectional"))
    )
    (net (code "65") (name "unconnected-(U1-P0.08-Pad26)") (class "Default")
      (node (ref "U1") (pin "26") (pinfunction "P0.08_26") (pintype "bidirectional"))
    )
    (net (code "66") (name "unconnected-(U1-P0.09-Pad27)") (class "Default")
      (node (ref "U1") (pin "27") (pinfunction "P0.09_27") (pintype "bidirectional"))
    )
    (net (code "67") (name "unconnected-(U1-P0.10-Pad28)") (class "Default")
      (node (ref "U1") (pin "28") (pinfunction "P0.10_28") (pintype "bidirectional"))
    )
    (net (code "68") (name "unconnected-(U1-P0.11-Pad29)") (class "Default")
      (node (ref "U1") (pin "29") (pinfunction "P0.11_29") (pintype "bidirectional"))
    )
    (net (code "69") (name "unconnected-(U1-P0.12-Pad30)") (class "Default")
      (node (ref "U1") (pin "30") (pinfunction "P0.12_30") (pintype "bidirectional"))
    )
    (net (code "70") (name "unconnected-(U1-P0.13-Pad31)") (class "Default")
      (node (ref "U1") (pin "31") (pinfunction "P0.13_31") (pintype "bidirectional"))
    )
    (net (code "71") (name "unconnected-(U1-P0.14-Pad32)") (class "Default")
      (node (ref "U1") (pin "32") (pinfunction "P0.14_32") (pintype "bidirectional"))
    )
    (net (code "72") (name "unconnected-(U1-P0.15-Pad33)") (class "Default")
      (node (ref "U1") (pin "33") (pinfunction "P0.15_33") (pintype "bidirectional"))
    )
    (net (code "73") (name "unconnected-(U1-P0.17-Pad37)") (class "Default")
      (node (ref "U1") (pin "37") (pinfunction "P0.17_37") (pintype "bidirectional"))
    )
    (net (code "74") (name "unconnected-(U1-P0.20-Pad40)") (class "Default")
      (node (ref "U1") (pin "40") (pinfunction "P0.20_40") (pintype "bidirectional"))
    )
    (net (code "75") (name "unconnected-(U1-P0.26{slash}AIN0{slash}XL2-Pad9)") (class "Default")
      (node (ref "U1") (pin "9") (pinfunction "P0.26/AIN0/XL2_9") (pintype "bidirectional"))
    )
    (net (code "76") (name "unconnected-(U1-P0.27{slash}AIN1{slash}XL1-Pad10)") (class "Default")
      (node (ref "U1") (pin "10") (pinfunction "P0.27/AIN1/XL1_10") (pintype "bidirectional"))
    )
    (net (code "77") (name "unconnected-(U1-P0.28-Pad11)") (class "Default")
      (node (ref "U1") (pin "11") (pinfunction "P0.28_11") (pintype "bidirectional"))
    )
    (net (code "78") (name "unconnected-(U1-P0.29-Pad12)") (class "Default")
      (node (ref "U1") (pin "12") (pinfunction "P0.29_12") (pintype "bidirectional"))
    )
    (net (code "79") (name "unconnected-(U2-P4-Pad4)") (class "Default")
      (node (ref "U2") (pin "4") (pinfunction "P4_4") (pintype "bidirectional"))
    )
    (net (code "80") (name "unconnected-(U4-PA13{slash}I13{slash}I2C{slash}SERCOM2+4.1-Pad22)") (class "Default")
      (node (ref "U4") (pin "22") (pinfunction "PA13/I13/I2C/SERCOM2+4.1_22") (pintype "bidirectional"))
    )
    (net (code "81") (name "unconnected-(U4-PA27{slash}I15-Pad39)") (class "Default")
      (node (ref "U4") (pin "39") (pinfunction "PA27/I15_39") (pintype "bidirectional"))
    )
    (net (code "82") (name "unconnected-(U4-PA28{slash}I8-Pad41)") (class "Default")
      (node (ref "U4") (pin "41") (pinfunction "PA28/I8_41") (pintype "bidirectional"))
    )
    (net (code "83") (name "unconnected-(U4-PB03{slash}I3{slash}AIN11{slash}SERCOM5.1-Pad48)") (class "Default")
      (node (ref "U4") (pin "48") (pinfunction "PB03/I3/AIN11/SERCOM5.1_48") (pintype "bidirectional"))
    )
    (net (code "84") (name "unconnected-(U4-PB22{slash}I6{slash}SERCOM5.2-Pad37)") (class "Default")
      (node (ref "U4") (pin "37") (pinfunction "PB22/I6/SERCOM5.2_37") (pintype "bidirectional"))
    )
    (net (code "85") (name "unconnected-(U4-PB23{slash}I7{slash}SERCOM5.3-Pad38)") (class "Default")
      (node (ref "U4") (pin "38") (pinfunction "PB23/I7/SERCOM5.3_38") (pintype "bidirectional"))
    )
    (net (code "86") (name "unconnected-(U25-Pad1')") (class "Default")
      (node (ref "U25") (pin "1'") (pinfunction "1'_1'") (pintype "bidirectional"))
    )
    (net (code "87") (name "unconnected-(U25-Pad2')") (class "Default")
      (node (ref "U25") (pin "2'") (pinfunction "2'_2'") (pintype "bidirectional"))
    )
    (net (code "88") (name "unconnected-(U41-Pad1')") (class "Default")
      (node (ref "U41") (pin "1'") (pinfunction "1'_1'") (pintype "bidirectional"))
    )
    (net (code "89") (name "unconnected-(U41-Pad2')") (class "Default")
      (node (ref "U41") (pin "2'") (pinfunction "2'_2'") (pintype "bidirectional"))
    )
    (net (code "90") (name "unconnected-(X3-PadID)") (class "Default")
      (node (ref "X3") (pin "ID") (pinfunction "ID_ID") (pintype "bidirectional"))
    )
  )
)
